# CAN.net
KiCad netlist of a schematic drawn in Altium Designer
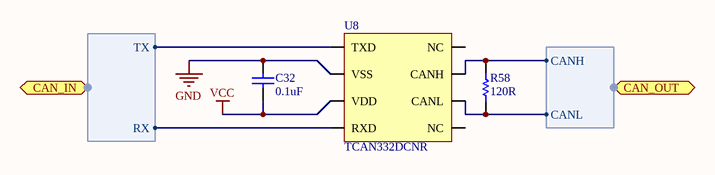
[diagram p0: CAN.SchDoc]

(export (version "E")
  (design (tool "Eeschema 10.0.6"))
  (components
    (comp (ref "C32")
      (value "0.1uF")
      (footprint "C0402[1005X55]")
      (description "0.1uF 6.3V 10% 0402 (1005 Metric)")
      (fields (field (name "TOLERANCE") "10%") (field (name "PARTNUMBER") "GRM155R70J104KA01D"))
      (libsource (lib "Capacitors") (part "CAP_0.1uF_6.3V_0402_10%"))
    )
    (comp (ref "R58")
      (value "120R")
      (footprint "R0402[1005]")
      (description "120R 0.063W 1% 0402 (1005 Metric)")
      (fields (field (name "TOLERANCE") "1%") (field (name "POWER") "0.063W"))
      (libsource (lib "Resistors") (part "RES_120R_0402_1%"))
    )
    (comp (ref "U8")
      (value "TCAN332DCNR")
      (footprint "SOT-23-8")
      (description "CAN Interface IC 3.3-V CAN Transceivers with CAN FD (Flexible Data Rate) 8-SOT-23 -40 to 125")
      (fields (field (name "MANUFACTURER") "Texas Instruments"))
      (libsource (lib "ICs") (part "TCAN332DCNR"))
    )
  )
  (nets
    (net (code "4") (name "/CANH") (class "Default")
      (node (ref "R58") (pin "2") (pinfunction "2_2") (pintype "passive"))
      (node (ref "U8") (pin "7") (pinfunction "CANH_7") (pintype "passive"))
    )
    (net (code "5") (name "/CANL") (class "Default")
      (node (ref "R58") (pin "1") (pinfunction "1_1") (pintype "passive"))
      (node (ref "U8") (pin "6") (pinfunction "CANL_6") (pintype "passive"))
    )
    (net (code "6") (name "/RX") (class "Default")
      (node (ref "U8") (pin "4") (pinfunction "RXD_4") (pintype "passive"))
    )
    (net (code "7") (name "/TX") (class "Default")
      (node (ref "U8") (pin "1") (pinfunction "TXD_1") (pintype "passive"))
    )
    (net (code "10") (name "GND") (class "Default")
      (node (ref "C32") (pin "1") (pinfunction "1_1") (pintype "passive"))
      (node (ref "U8") (pin "2") (pinfunction "VSS_2") (pintype "passive"))
    )
    (net (code "11") (name "VCC") (class "Default")
      (node (ref "C32") (pin "2") (pinfunction "2_2") (pintype "passive"))
      (node (ref "U8") (pin "3") (pinfunction "VDD_3") (pintype "passive"))
    )
    (net (code "12") (name "unconnected-(U8-NC-Pad5)") (class "Default")
      (node (ref "U8") (pin "5") (pinfunction "NC_5") (pintype "passive"))
    )
    (net (code "13") (name "unconnected-(U8-NC-Pad8)") (class "Default")
      (node (ref "U8") (pin "8") (pinfunction "NC_8") (pintype "passive"))
    )
  )
)
